# LandCruiser-Controller_1V0.net
KiCad netlist of a schematic drawn in EAGLE
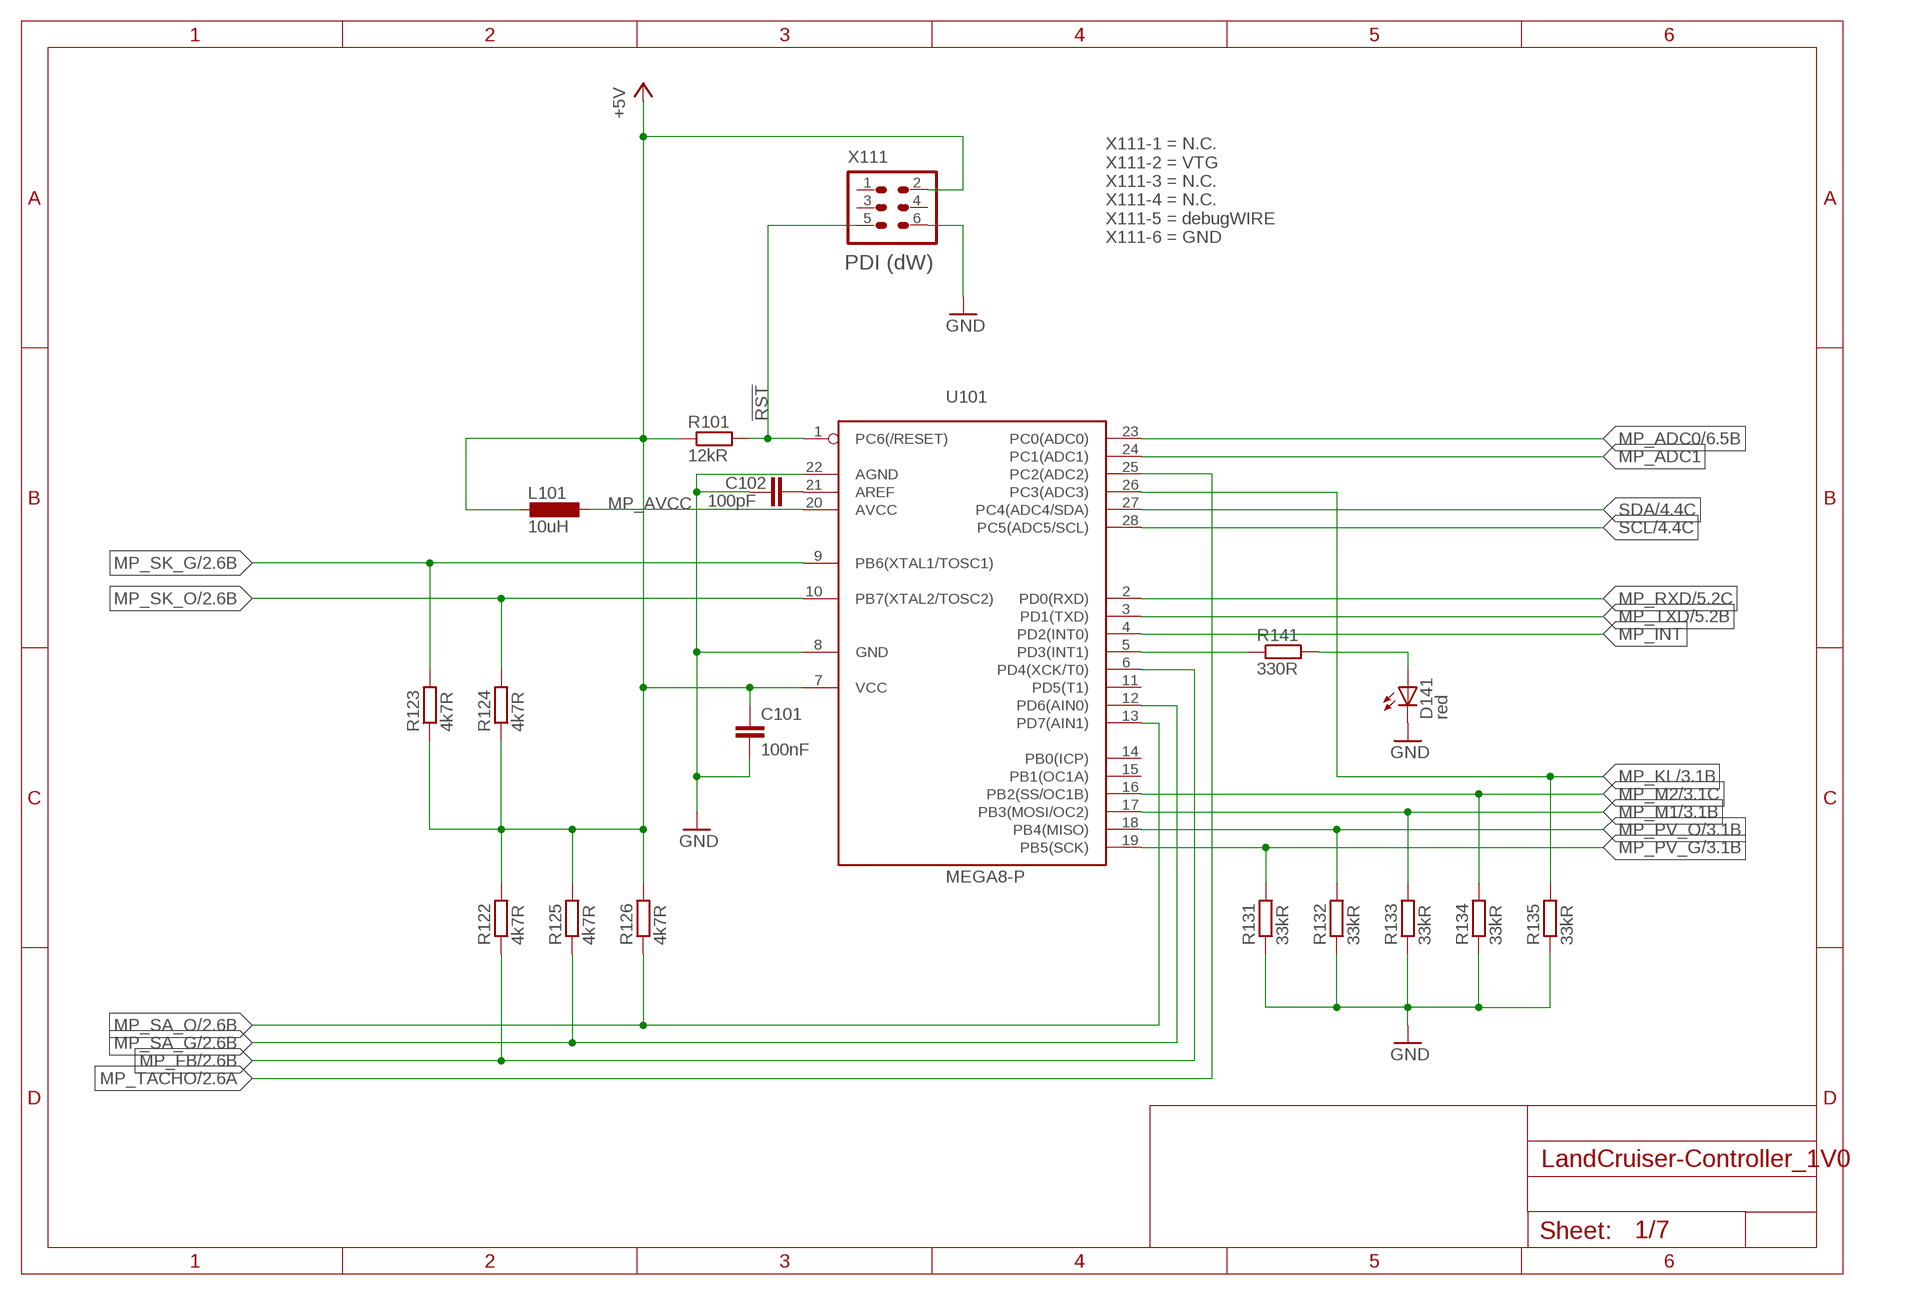
[diagram p0: schematic, sheet 1]
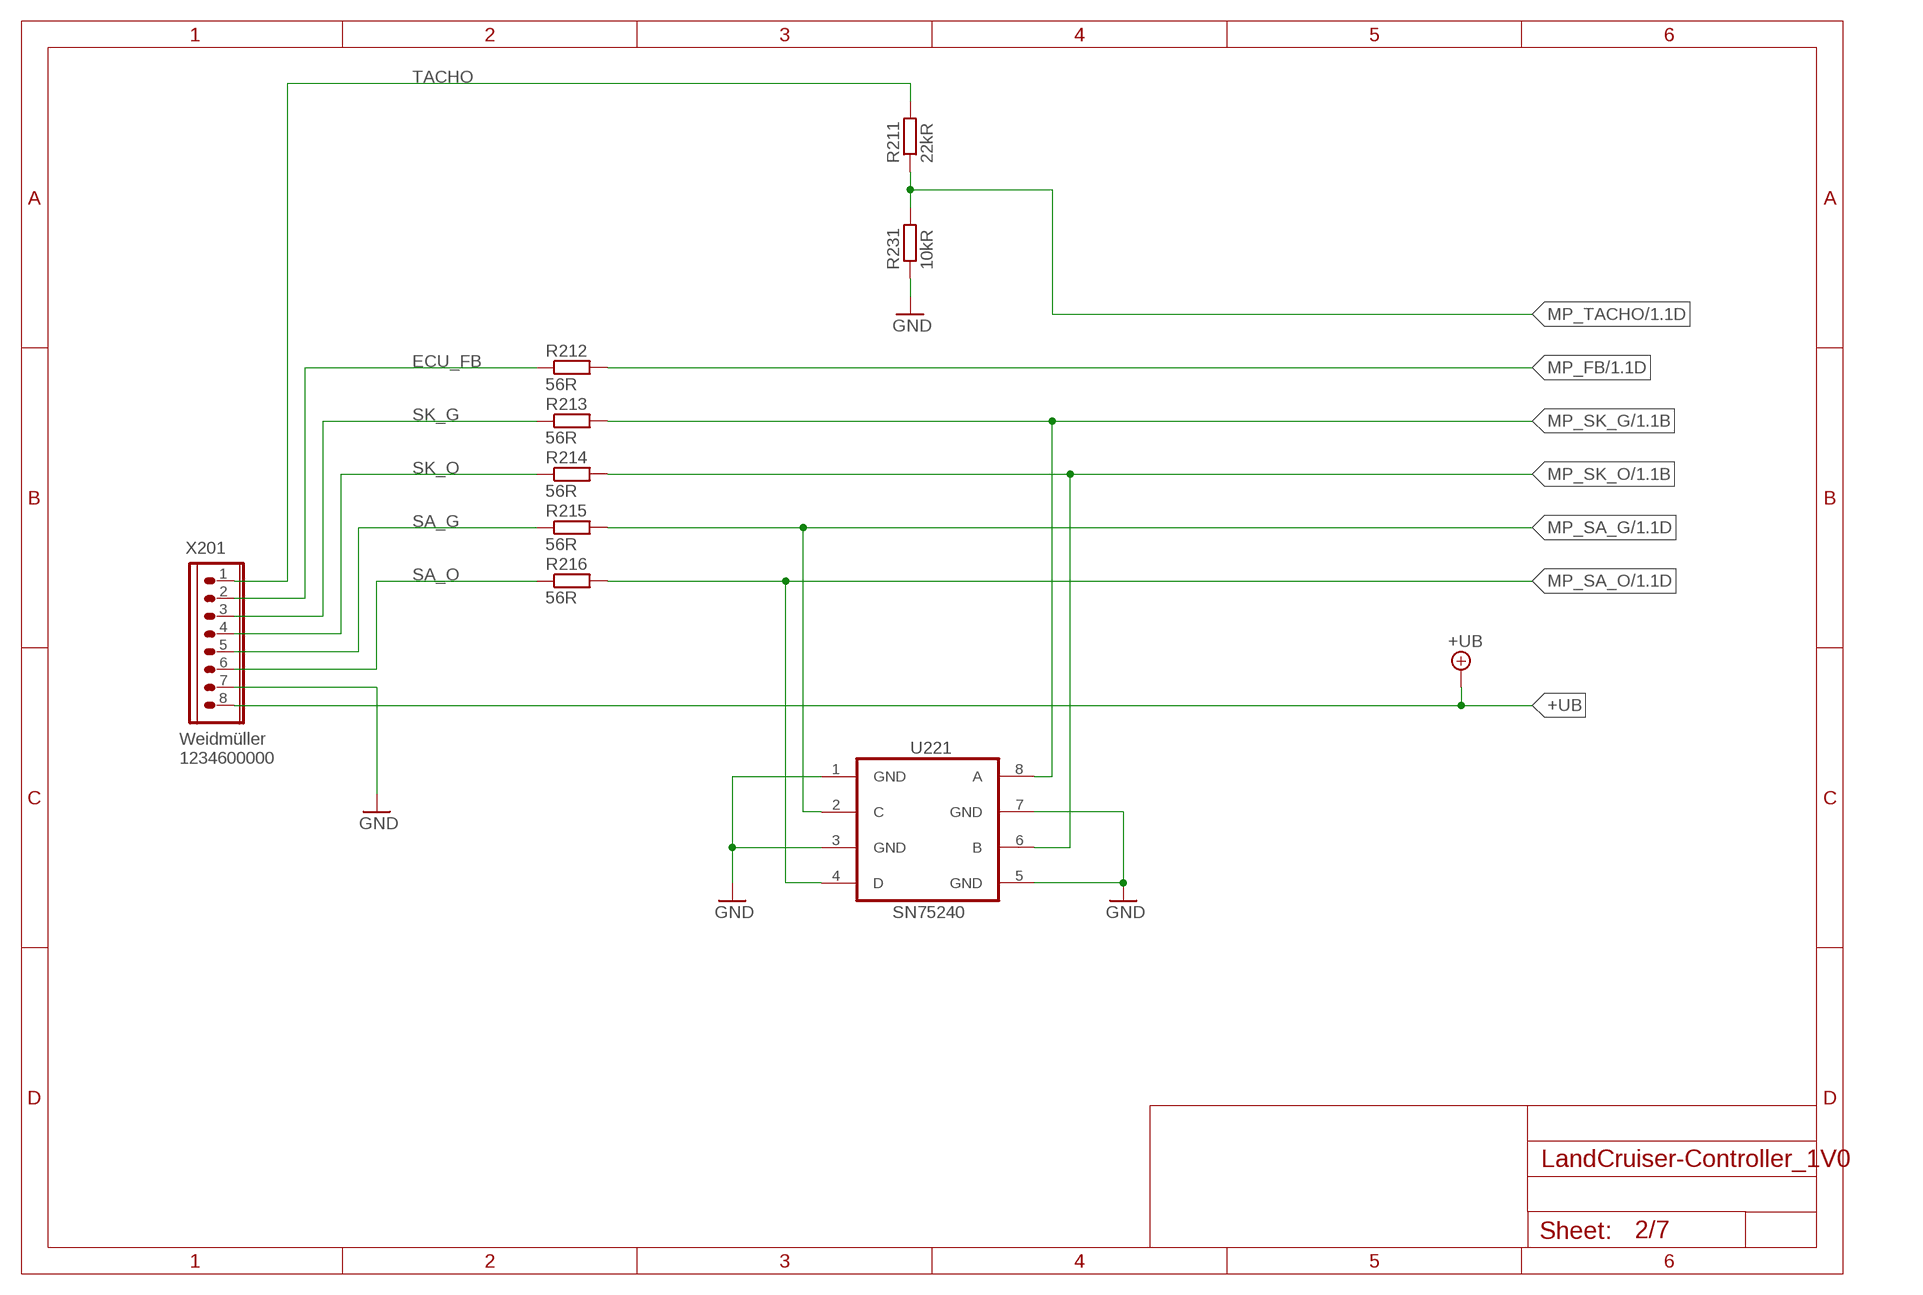
[diagram p1: schematic, sheet 2]
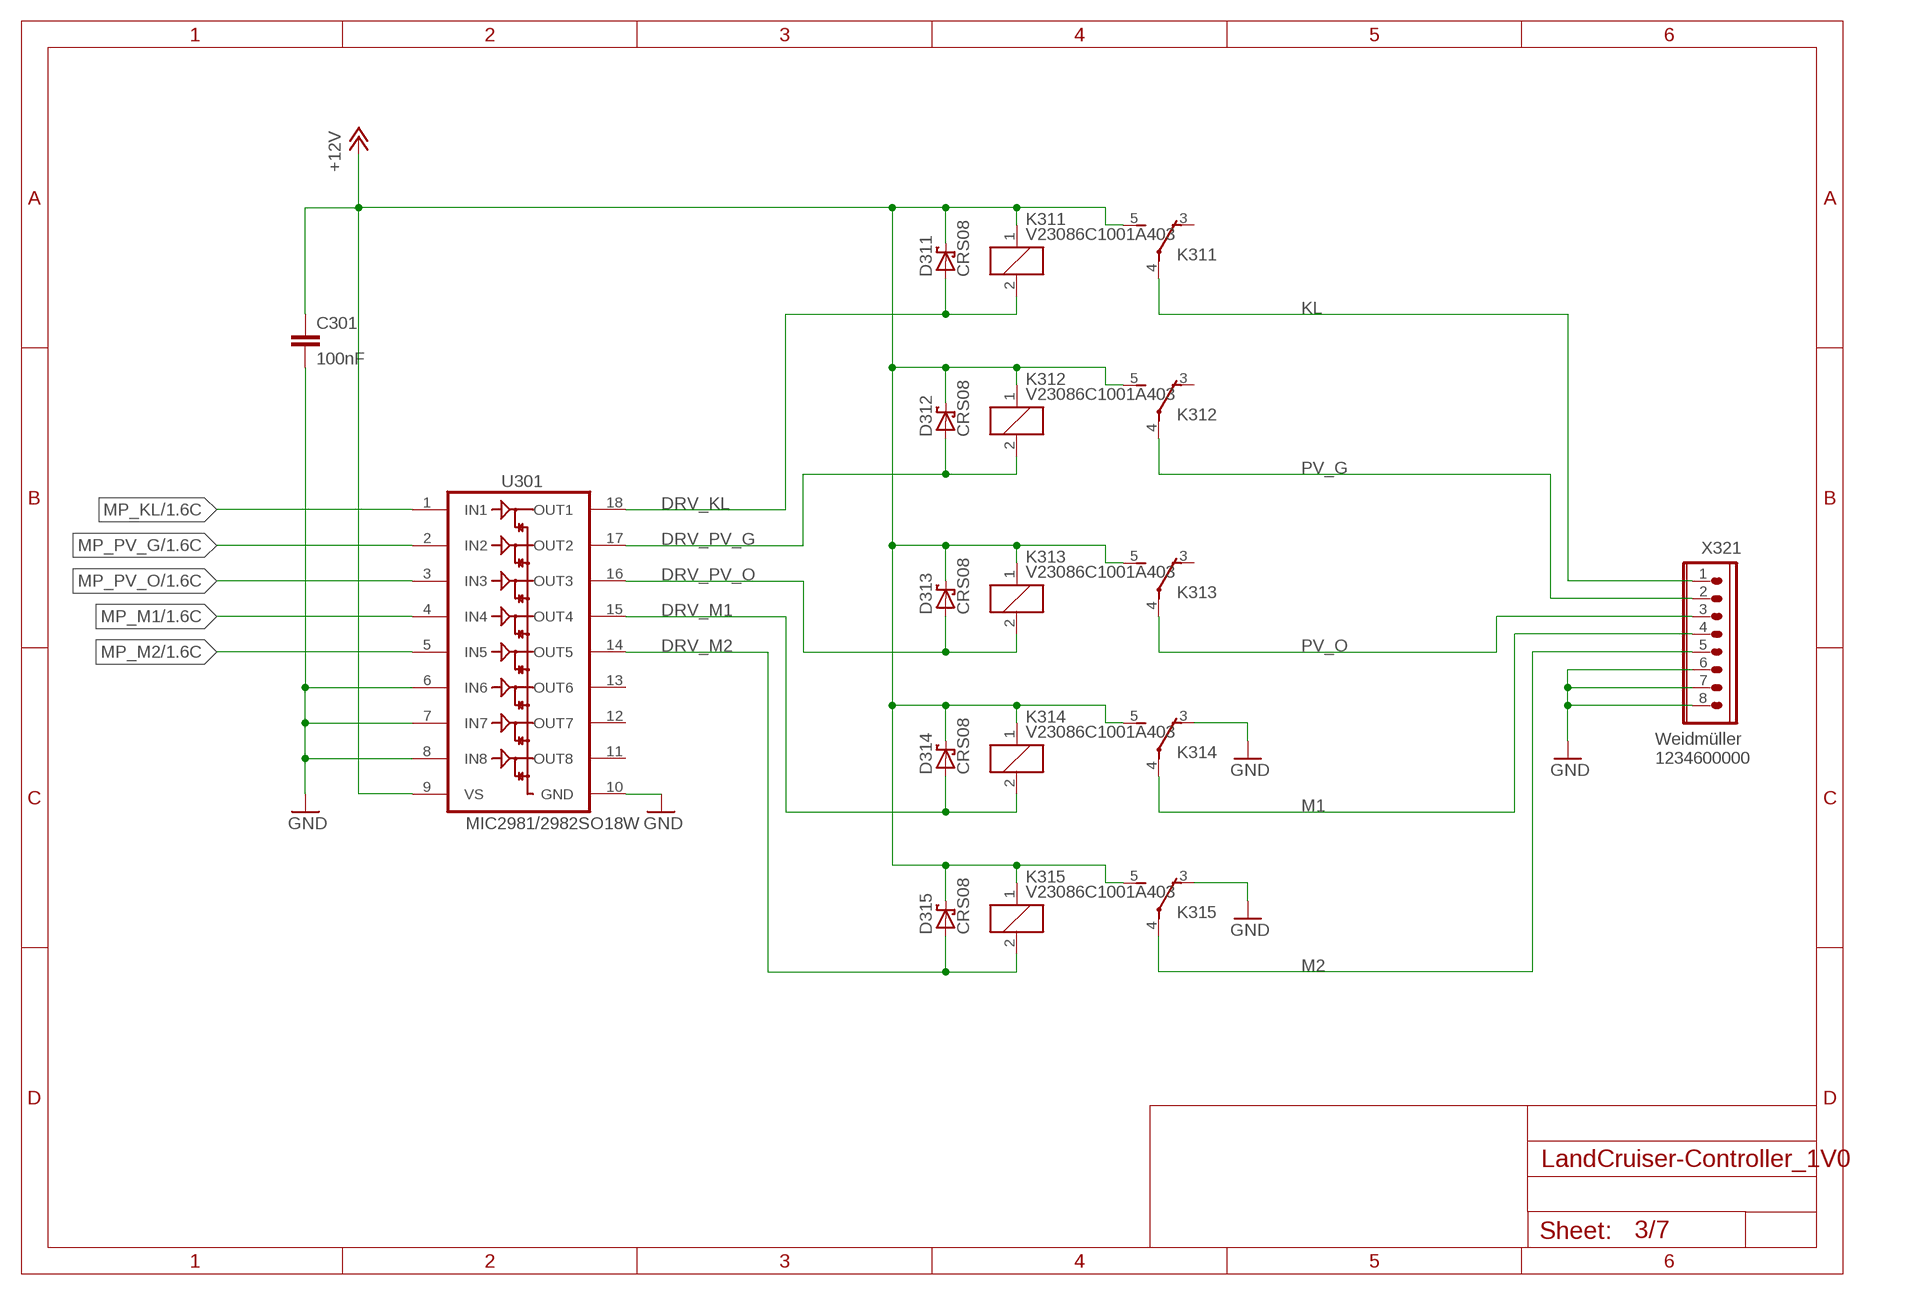
[diagram p2: schematic, sheet 3]
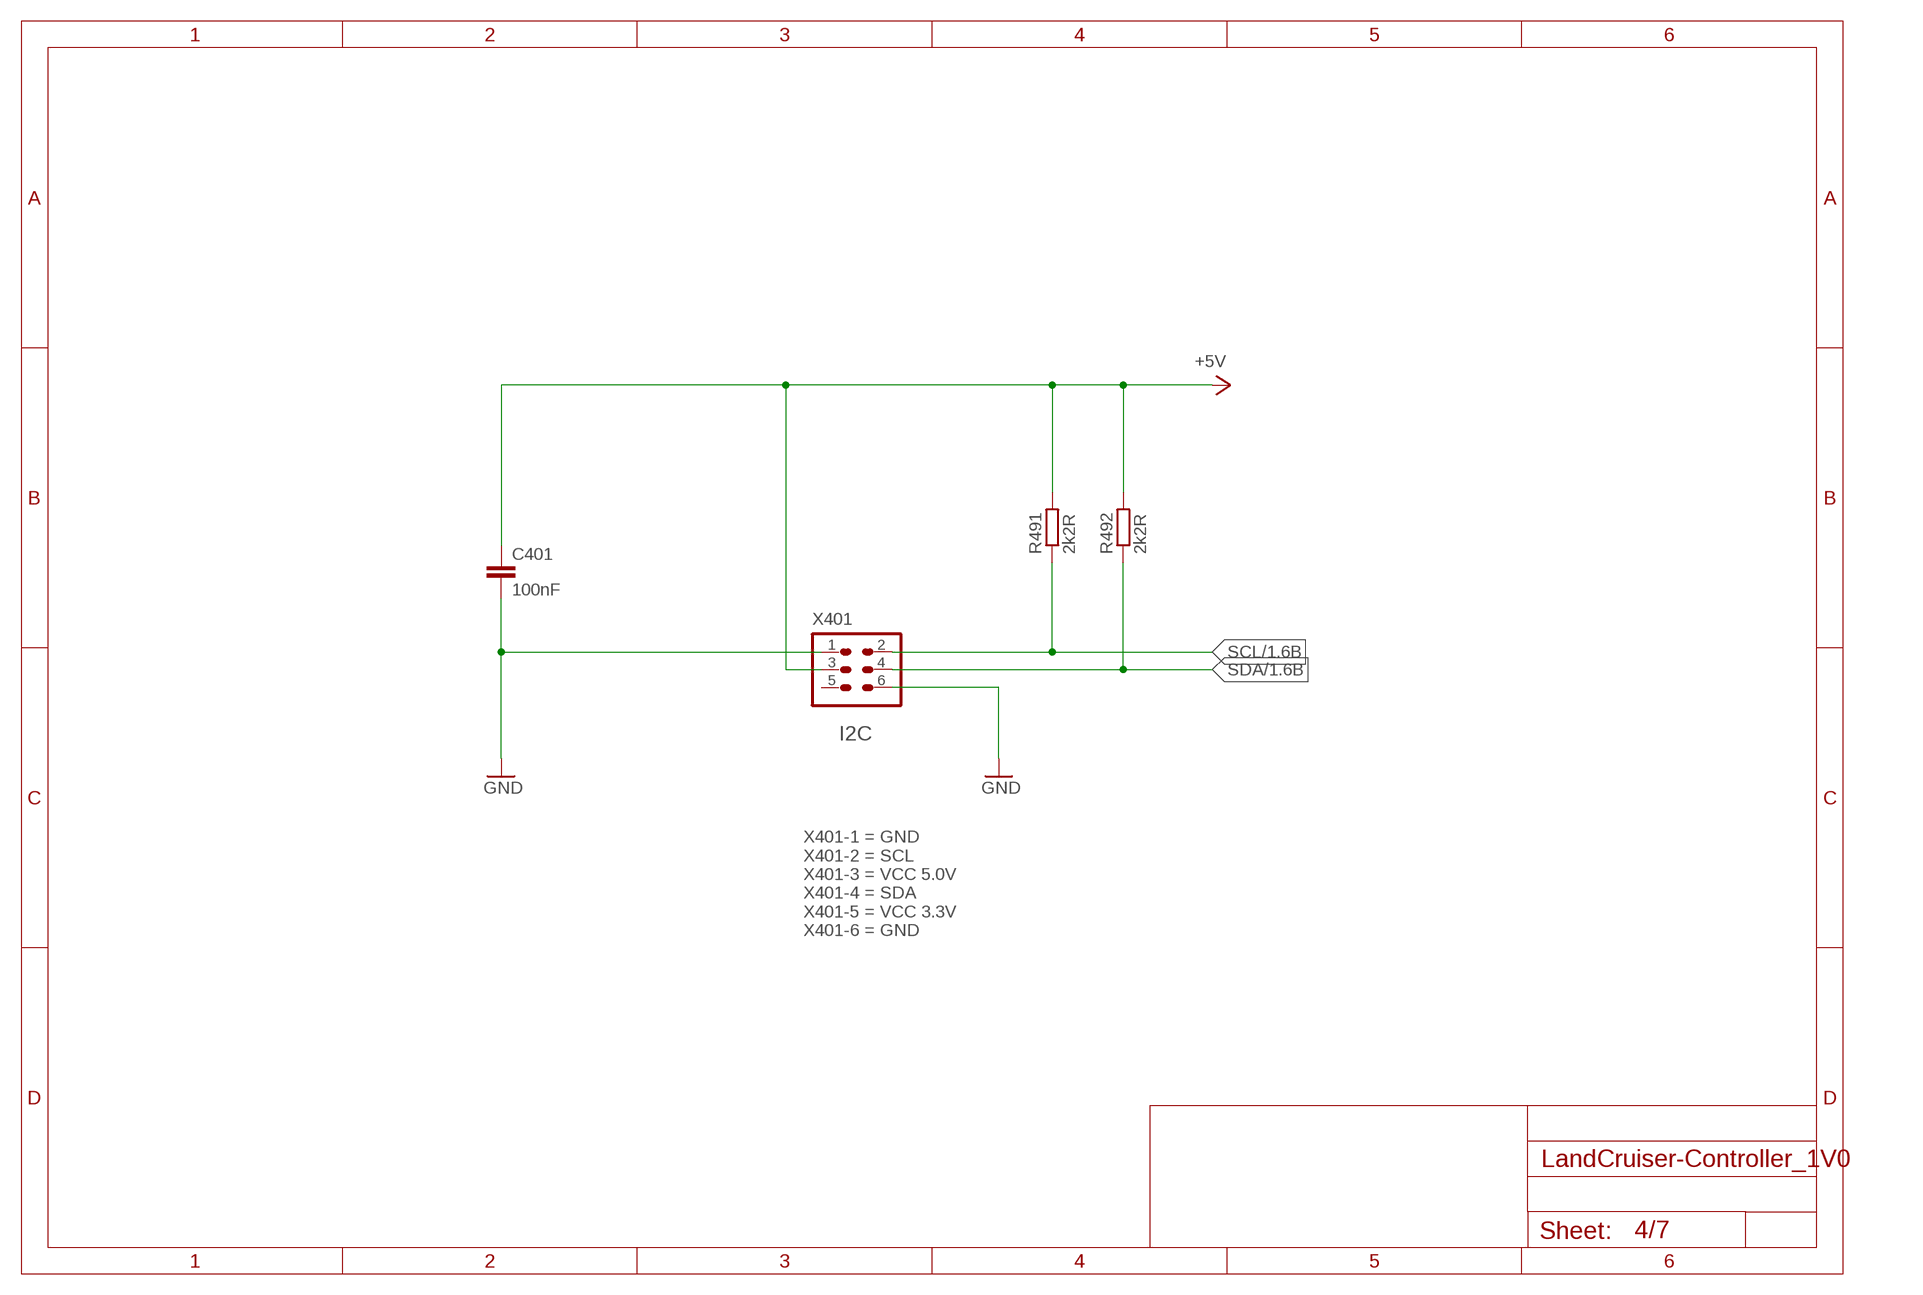
[diagram p3: schematic, sheet 4]
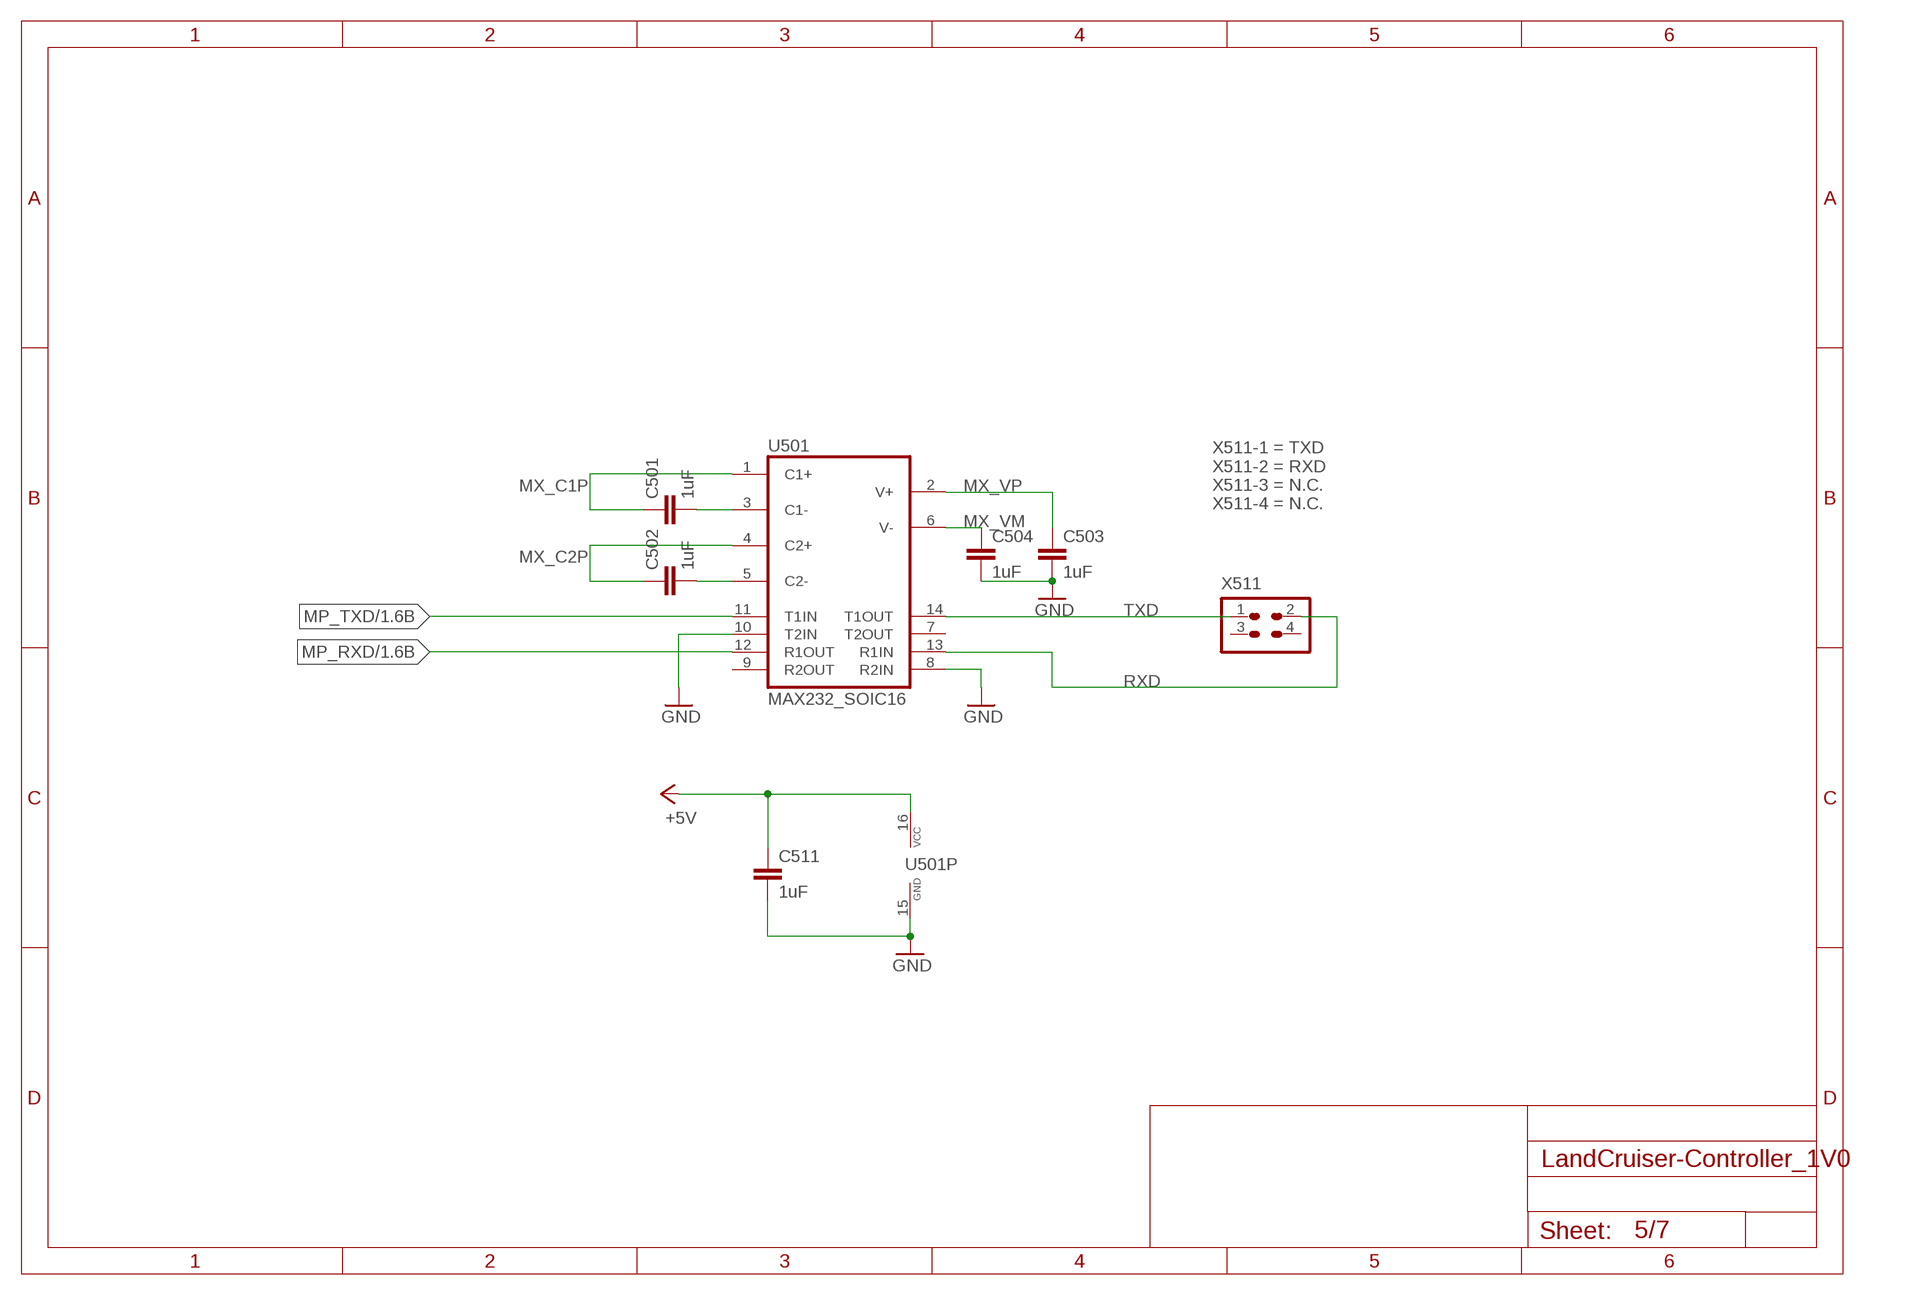
[diagram p4: schematic, sheet 5]
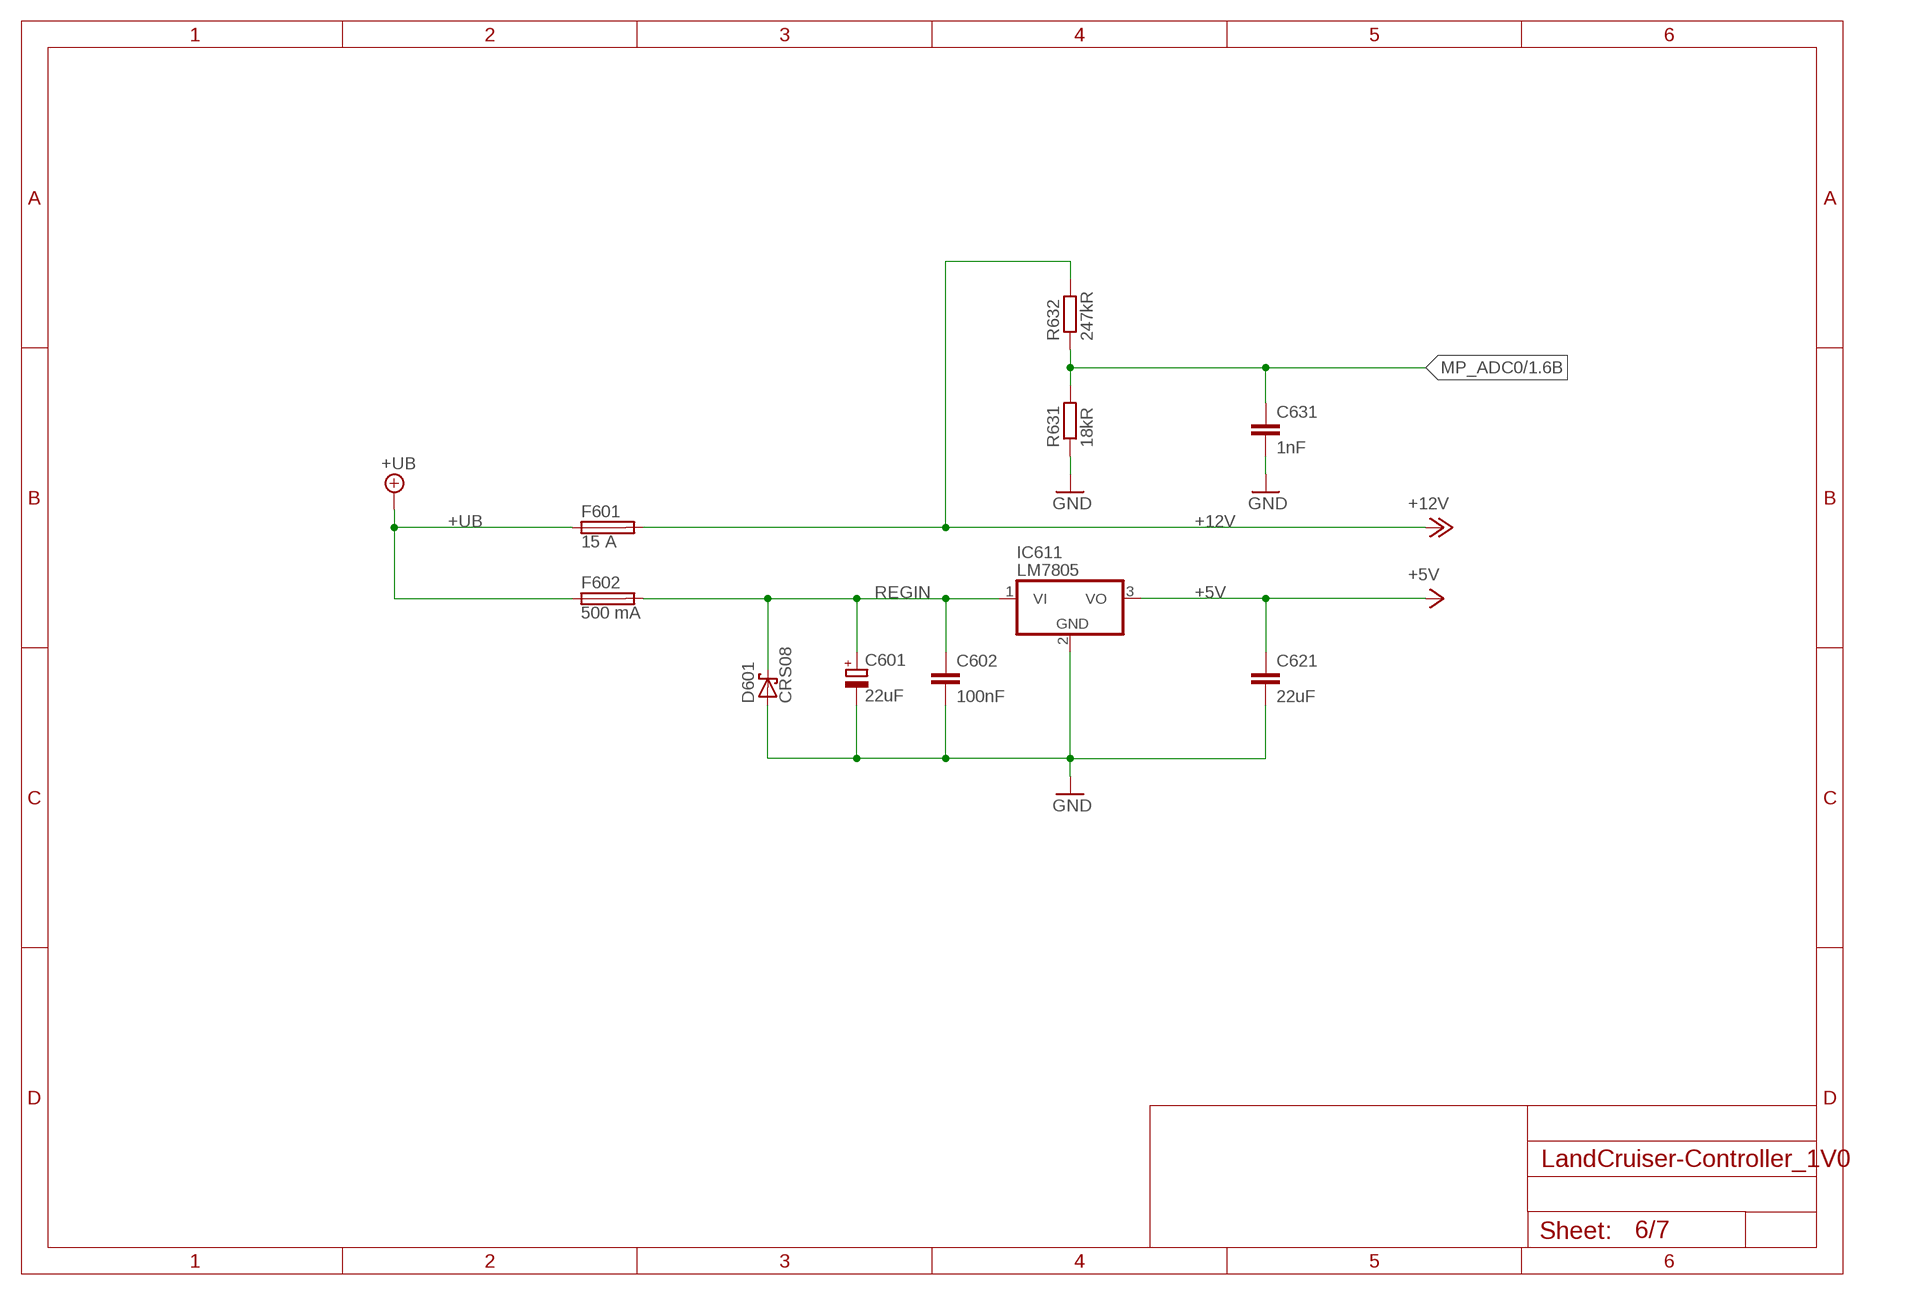
[diagram p5: schematic, sheet 6]
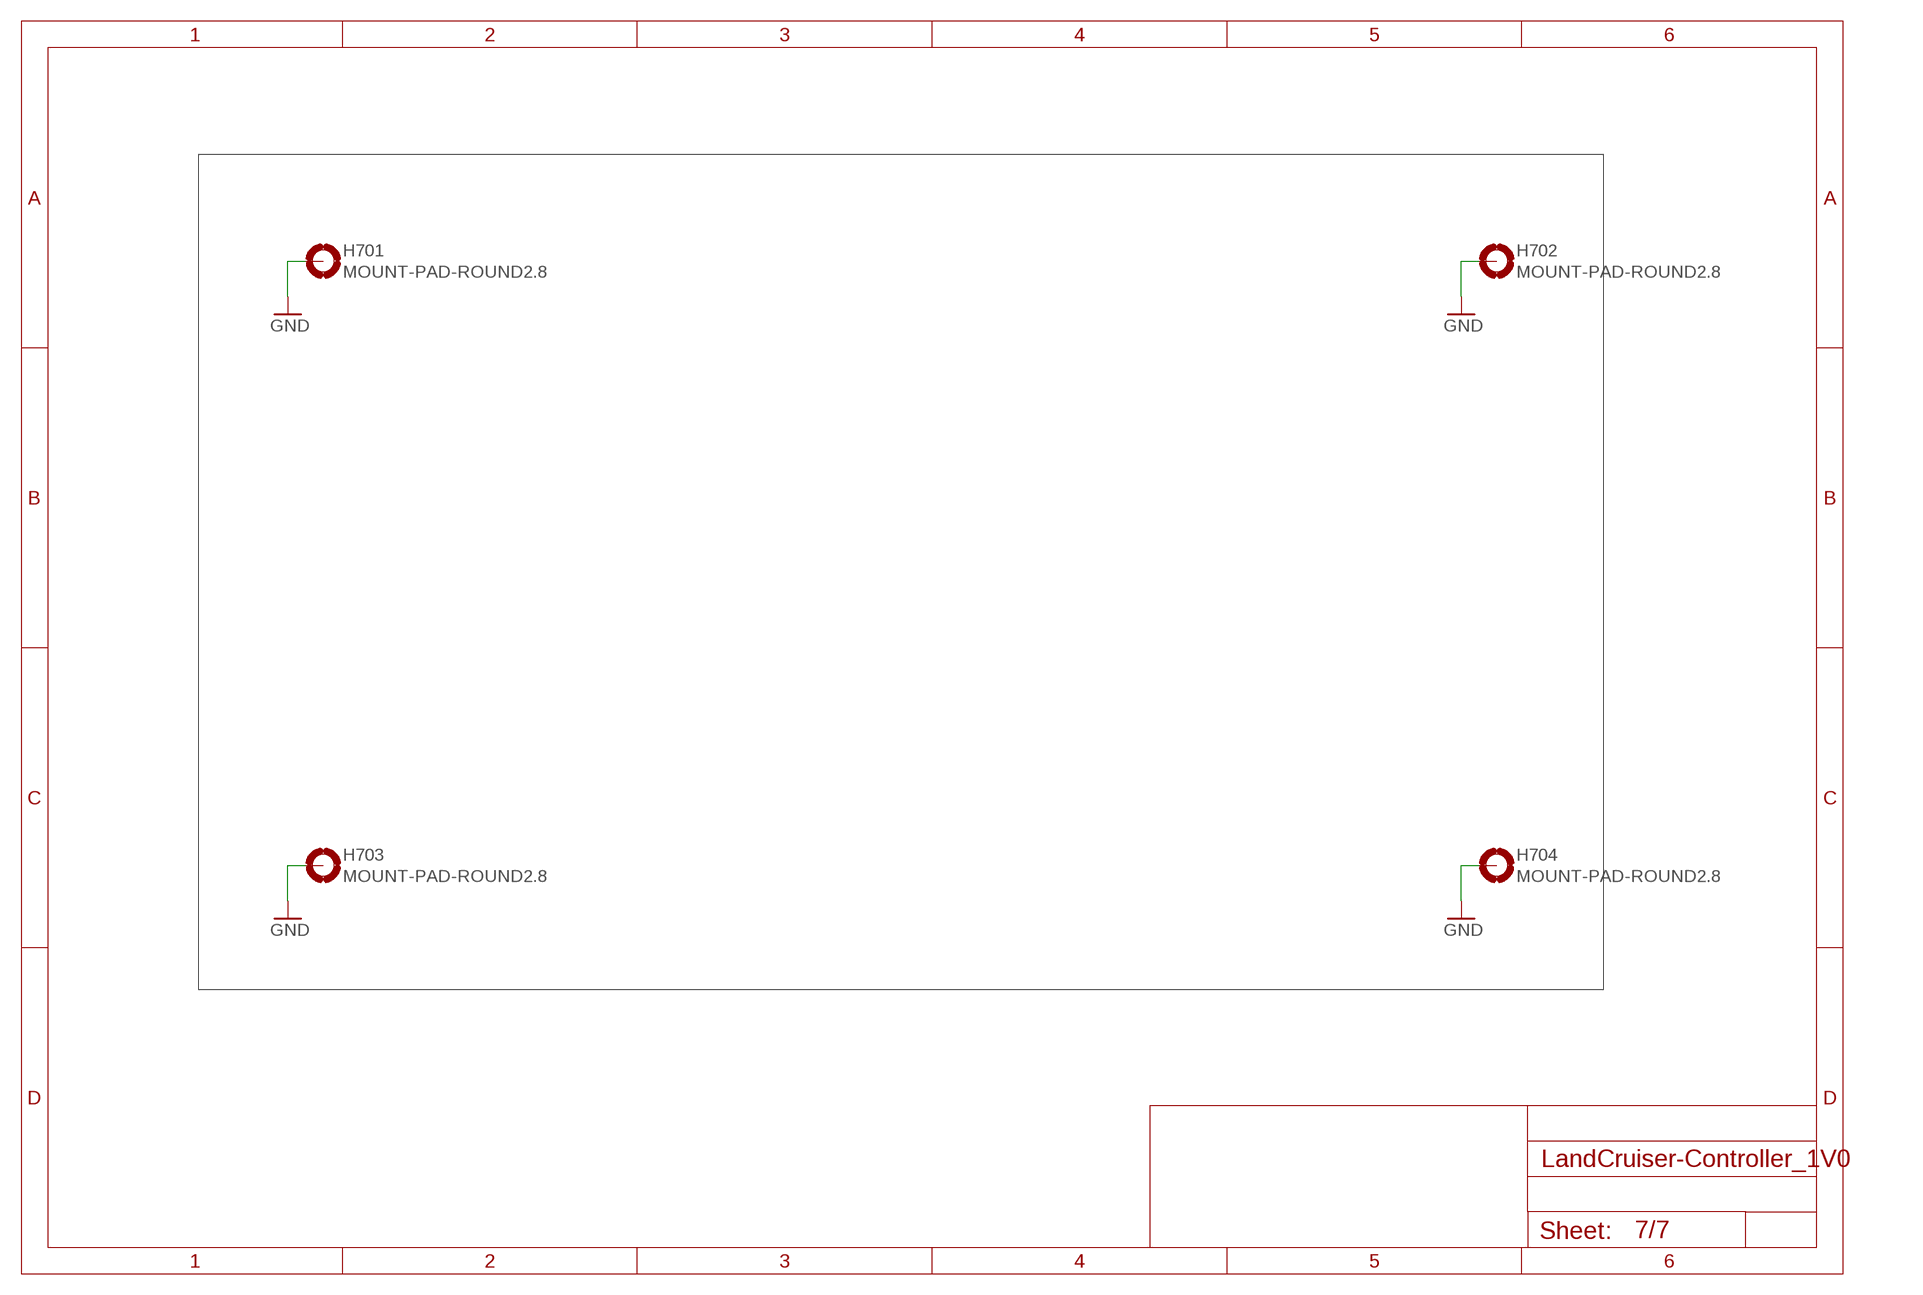
[diagram p6: schematic, sheet 7]

(export (version "E")
  (design (tool "Eeschema 10.0.6"))
  (components
    (comp (ref "C101")
      (value "100nF")
      (footprint "eagle-import:C0805")
      (libsource (lib "eagle-import") (part "C-EUC0805"))
    )
    (comp (ref "C102")
      (value "100pF")
      (footprint "eagle-import:C0805")
      (libsource (lib "eagle-import") (part "C-EUC0805"))
    )
    (comp (ref "D141")
      (value "red")
      (footprint "eagle-import:LED_2PIN-TTH")
      (libsource (lib "eagle-import") (part "LED"))
    )
    (comp (ref "L101")
      (value "10uH")
      (footprint "eagle-import:L1812")
      (libsource (lib "eagle-import") (part "L-EUL1812"))
    )
    (comp (ref "R101")
      (value "12kR")
      (footprint "eagle-import:R0805")
      (libsource (lib "eagle-import") (part "R-EU_R0805"))
    )
    (comp (ref "R122")
      (value "4k7R")
      (footprint "eagle-import:R0805")
      (libsource (lib "eagle-import") (part "R-EU_R0805"))
    )
    (comp (ref "R123")
      (value "4k7R")
      (footprint "eagle-import:R0805")
      (libsource (lib "eagle-import") (part "R-EU_R0805"))
    )
    (comp (ref "R124")
      (value "4k7R")
      (footprint "eagle-import:R0805")
      (libsource (lib "eagle-import") (part "R-EU_R0805"))
    )
    (comp (ref "R125")
      (value "4k7R")
      (footprint "eagle-import:R0805")
      (libsource (lib "eagle-import") (part "R-EU_R0805"))
    )
    (comp (ref "R126")
      (value "4k7R")
      (footprint "eagle-import:R0805")
      (libsource (lib "eagle-import") (part "R-EU_R0805"))
    )
    (comp (ref "R131")
      (value "33kR")
      (footprint "eagle-import:R0805")
      (libsource (lib "eagle-import") (part "R-EU_R0805"))
    )
    (comp (ref "R132")
      (value "33kR")
      (footprint "eagle-import:R0805")
      (libsource (lib "eagle-import") (part "R-EU_R0805"))
    )
    (comp (ref "R133")
      (value "33kR")
      (footprint "eagle-import:R0805")
      (libsource (lib "eagle-import") (part "R-EU_R0805"))
    )
    (comp (ref "R134")
      (value "33kR")
      (footprint "eagle-import:R0805")
      (libsource (lib "eagle-import") (part "R-EU_R0805"))
    )
    (comp (ref "R135")
      (value "33kR")
      (footprint "eagle-import:R0805")
      (libsource (lib "eagle-import") (part "R-EU_R0805"))
    )
    (comp (ref "R141")
      (value "330R")
      (footprint "eagle-import:R0805")
      (libsource (lib "eagle-import") (part "R-EU_R0805"))
    )
    (comp (ref "U101")
      (value "MEGA8-P")
      (footprint "eagle-import:DIL28-3")
      (libsource (lib "eagle-import") (part "MEGA8-P"))
    )
    (comp (ref "X111")
      (value "HEADER-2X3")
      (footprint "eagle-import:2X03")
      (libsource (lib "eagle-import") (part "HEADER-2X3"))
    )
    (comp (ref "C301")
      (value "100nF")
      (footprint "eagle-import:C0805")
      (libsource (lib "eagle-import") (part "C-EUC0805"))
    )
    (comp (ref "D311")
      (value "CRS08")
      (footprint "eagle-import:SOD80C")
      (libsource (lib "eagle-import") (part "CRS08"))
    )
    (comp (ref "D312")
      (value "CRS08")
      (footprint "eagle-import:SOD80C")
      (libsource (lib "eagle-import") (part "CRS08"))
    )
    (comp (ref "D313")
      (value "CRS08")
      (footprint "eagle-import:SOD80C")
      (libsource (lib "eagle-import") (part "CRS08"))
    )
    (comp (ref "D314")
      (value "CRS08")
      (footprint "eagle-import:SOD80C")
      (libsource (lib "eagle-import") (part "CRS08"))
    )
    (comp (ref "D315")
      (value "CRS08")
      (footprint "eagle-import:SOD80C")
      (libsource (lib "eagle-import") (part "CRS08"))
    )
    (comp (ref "K311")
      (value "V23086C1001A403")
      (footprint "eagle-import:V23086-CO")
      (libsource (lib "eagle-import") (part "V23086C1001A403"))
    )
    (comp (ref "K312")
      (value "V23086C1001A403")
      (footprint "eagle-import:V23086-CO")
      (libsource (lib "eagle-import") (part "V23086C1001A403"))
    )
    (comp (ref "K313")
      (value "V23086C1001A403")
      (footprint "eagle-import:V23086-CO")
      (libsource (lib "eagle-import") (part "V23086C1001A403"))
    )
    (comp (ref "K314")
      (value "V23086C1001A403")
      (footprint "eagle-import:V23086-CO")
      (libsource (lib "eagle-import") (part "V23086C1001A403"))
    )
    (comp (ref "K315")
      (value "V23086C1001A403")
      (footprint "eagle-import:V23086-CO")
      (libsource (lib "eagle-import") (part "V23086C1001A403"))
    )
    (comp (ref "U301")
      (value "MIC2981/2982SO18W")
      (footprint "eagle-import:SO-18W")
      (fields (field (name "MF") "MICROCHIP") (field (name "MP") "MIC2981/82YWM-TR"))
      (libsource (lib "eagle-import") (part "MIC2981/2982SO18W"))
    )
    (comp (ref "X321")
      (value "WEIDMUELLER 1234600000")
      (footprint "eagle-import:WIRE-TO-BOARD_5MM08_1X08")
      (libsource (lib "eagle-import") (part "WIRE-TO-BOARD_5MM08_1X08"))
    )
    (comp (ref "C401")
      (value "100nF")
      (footprint "eagle-import:C0805")
      (libsource (lib "eagle-import") (part "C-EUC0805"))
    )
    (comp (ref "R491")
      (value "2k2R")
      (footprint "eagle-import:R0805")
      (libsource (lib "eagle-import") (part "R-EU_R0805"))
    )
    (comp (ref "R492")
      (value "2k2R")
      (footprint "eagle-import:R0805")
      (libsource (lib "eagle-import") (part "R-EU_R0805"))
    )
    (comp (ref "X401")
      (value "I2C")
      (footprint "eagle-import:2X03")
      (libsource (lib "eagle-import") (part "HEADER-2X3"))
    )
    (comp (ref "R211")
      (value "22kR")
      (footprint "eagle-import:R0805")
      (libsource (lib "eagle-import") (part "R-EU_R0805"))
    )
    (comp (ref "R212")
      (value "56R")
      (footprint "eagle-import:R0805")
      (libsource (lib "eagle-import") (part "R-EU_R0805"))
    )
    (comp (ref "R213")
      (value "56R")
      (footprint "eagle-import:R0805")
      (libsource (lib "eagle-import") (part "R-EU_R0805"))
    )
    (comp (ref "R214")
      (value "56R")
      (footprint "eagle-import:R0805")
      (libsource (lib "eagle-import") (part "R-EU_R0805"))
    )
    (comp (ref "R215")
      (value "56R")
      (footprint "eagle-import:R0805")
      (libsource (lib "eagle-import") (part "R-EU_R0805"))
    )
    (comp (ref "R216")
      (value "56R")
      (footprint "eagle-import:R0805")
      (libsource (lib "eagle-import") (part "R-EU_R0805"))
    )
    (comp (ref "R231")
      (value "10kR")
      (footprint "eagle-import:R0805")
      (libsource (lib "eagle-import") (part "R-EU_R0805"))
    )
    (comp (ref "U221")
      (value "SN75240")
      (footprint "eagle-import:TSSOP-8")
      (libsource (lib "eagle-import") (part "SN75240"))
    )
    (comp (ref "X201")
      (value "WEIDMUELLER 1234600000")
      (footprint "eagle-import:WIRE-TO-BOARD_5MM08_1X08")
      (libsource (lib "eagle-import") (part "WIRE-TO-BOARD_5MM08_1X08"))
    )
    (comp (ref "C601")
      (value "22uF")
      (footprint "eagle-import:E2,5-7")
      (libsource (lib "eagle-import") (part "CPOL-EUE2.5-7"))
    )
    (comp (ref "C602")
      (value "100nF")
      (footprint "eagle-import:C0805")
      (libsource (lib "eagle-import") (part "C-EUC0805"))
    )
    (comp (ref "C621")
      (value "22uF")
      (footprint "eagle-import:C0805")
      (libsource (lib "eagle-import") (part "C-EUC0805"))
    )
    (comp (ref "C631")
      (value "1nF")
      (footprint "eagle-import:C0805")
      (libsource (lib "eagle-import") (part "C-EUC0805"))
    )
    (comp (ref "D601")
      (value "CRS08")
      (footprint "eagle-import:SOD80C")
      (libsource (lib "eagle-import") (part "CRS08"))
    )
    (comp (ref "F601")
      (value "15 A")
      (footprint "eagle-import:MCCQ-121")
      (fields (field (name "MF") "MINICOMP") (field (name "MPN") "MCCQ-121"))
      (libsource (lib "eagle-import") (part "MCCQ-121"))
    )
    (comp (ref "F602")
      (value "500 mA")
      (footprint "eagle-import:MCCQ-121")
      (fields (field (name "MF") "MINICOMP") (field (name "MPN") "MCCQ-121"))
      (libsource (lib "eagle-import") (part "MCCQ-121"))
    )
    (comp (ref "IC611")
      (value "LM7805")
      (footprint "eagle-import:TO220H")
      (libsource (lib "eagle-import") (part "78T05"))
    )
    (comp (ref "R631")
      (value "18kR")
      (footprint "eagle-import:R0805")
      (libsource (lib "eagle-import") (part "R-EU_R0805"))
    )
    (comp (ref "R632")
      (value "247kR")
      (footprint "eagle-import:R0805")
      (libsource (lib "eagle-import") (part "R-EU_R0805"))
    )
    (comp (ref "C501")
      (value "1uF")
      (footprint "eagle-import:C0805")
      (libsource (lib "eagle-import") (part "C-EUC0805"))
    )
    (comp (ref "C502")
      (value "1uF")
      (footprint "eagle-import:C0805")
      (libsource (lib "eagle-import") (part "C-EUC0805"))
    )
    (comp (ref "C503")
      (value "1uF")
      (footprint "eagle-import:C0805")
      (libsource (lib "eagle-import") (part "C-EUC0805"))
    )
    (comp (ref "C504")
      (value "1uF")
      (footprint "eagle-import:C0805")
      (libsource (lib "eagle-import") (part "C-EUC0805"))
    )
    (comp (ref "C511")
      (value "1uF")
      (footprint "eagle-import:C0805")
      (libsource (lib "eagle-import") (part "C-EUC0805"))
    )
    (comp (ref "U501")
      (value "MAX232_SOIC16")
      (footprint "eagle-import:SOIC16N")
      (fields (field (name "MF") "MAXIM") (field (name "MPN") "MAX232ECDR"))
      (libsource (lib "eagle-import") (part "MAX232_SOIC16"))
    )
    (comp (ref "X511")
      (value "HEADER-2X2")
      (footprint "eagle-import:2X02")
      (libsource (lib "eagle-import") (part "HEADER-2X2"))
    )
    (comp (ref "H701")
      (value "MOUNT-PAD-ROUND2.8")
      (footprint "eagle-import:2,8-PAD")
      (libsource (lib "eagle-import") (part "MOUNT-PAD-ROUND2.8"))
    )
    (comp (ref "H702")
      (value "MOUNT-PAD-ROUND2.8")
      (footprint "eagle-import:2,8-PAD")
      (libsource (lib "eagle-import") (part "MOUNT-PAD-ROUND2.8"))
    )
    (comp (ref "H703")
      (value "MOUNT-PAD-ROUND2.8")
      (footprint "eagle-import:2,8-PAD")
      (libsource (lib "eagle-import") (part "MOUNT-PAD-ROUND2.8"))
    )
    (comp (ref "H704")
      (value "MOUNT-PAD-ROUND2.8")
      (footprint "eagle-import:2,8-PAD")
      (libsource (lib "eagle-import") (part "MOUNT-PAD-ROUND2.8"))
    )
  )
  (nets
    (net (code "1") (name "+5V") (class "Default")
      (node (ref "C101") (pin "1") (pinfunction "1_1") (pintype "passive"))
      (node (ref "C401") (pin "1") (pinfunction "1_1") (pintype "passive"))
      (node (ref "C511") (pin "1") (pinfunction "1_1") (pintype "passive"))
      (node (ref "C621") (pin "1") (pinfunction "1_1") (pintype "passive"))
      (node (ref "IC611") (pin "3") (pinfunction "VO_3") (pintype "passive"))
      (node (ref "L101") (pin "2") (pinfunction "2_2") (pintype "passive"))
      (node (ref "R101") (pin "1") (pinfunction "1_1") (pintype "passive"))
      (node (ref "R122") (pin "2") (pinfunction "2_2") (pintype "passive"))
      (node (ref "R123") (pin "1") (pinfunction "1_1") (pintype "passive"))
      (node (ref "R124") (pin "1") (pinfunction "1_1") (pintype "passive"))
      (node (ref "R125") (pin "2") (pinfunction "2_2") (pintype "passive"))
      (node (ref "R126") (pin "2") (pinfunction "2_2") (pintype "passive"))
      (node (ref "R491") (pin "2") (pinfunction "2_2") (pintype "passive"))
      (node (ref "R492") (pin "2") (pinfunction "2_2") (pintype "passive"))
      (node (ref "U101") (pin "7") (pinfunction "VCC_7") (pintype "bidirectional"))
      (node (ref "U501") (pin "16") (pinfunction "VCC_16") (pintype "power_in"))
      (node (ref "X111") (pin "2") (pinfunction "2_2") (pintype "passive"))
      (node (ref "X401") (pin "3") (pinfunction "3_3") (pintype "passive"))
    )
    (net (code "2") (name "+12V") (class "Default")
      (node (ref "C301") (pin "1") (pinfunction "1_1") (pintype "passive"))
      (node (ref "D311") (pin "C") (pinfunction "C_C") (pintype "passive"))
      (node (ref "D312") (pin "C") (pinfunction "C_C") (pintype "passive"))
      (node (ref "D313") (pin "C") (pinfunction "C_C") (pintype "passive"))
      (node (ref "D314") (pin "C") (pinfunction "C_C") (pintype "passive"))
      (node (ref "D315") (pin "C") (pinfunction "C_C") (pintype "passive"))
      (node (ref "F601") (pin "3") (pinfunction "2_3") (pintype "passive"))
      (node (ref "F601") (pin "4") (pinfunction "2_4") (pintype "passive"))
      (node (ref "K311") (pin "1") (pinfunction "1_1") (pintype "passive"))
      (node (ref "K311") (pin "5") (pinfunction "S_5") (pintype "passive"))
      (node (ref "K312") (pin "1") (pinfunction "1_1") (pintype "passive"))
      (node (ref "K312") (pin "5") (pinfunction "S_5") (pintype "passive"))
      (node (ref "K313") (pin "1") (pinfunction "1_1") (pintype "passive"))
      (node (ref "K313") (pin "5") (pinfunction "S_5") (pintype "passive"))
      (node (ref "K314") (pin "1") (pinfunction "1_1") (pintype "passive"))
      (node (ref "K314") (pin "5") (pinfunction "S_5") (pintype "passive"))
      (node (ref "K315") (pin "1") (pinfunction "1_1") (pintype "passive"))
      (node (ref "K315") (pin "5") (pinfunction "S_5") (pintype "passive"))
      (node (ref "R632") (pin "2") (pinfunction "2_2") (pintype "passive"))
      (node (ref "U301") (pin "9") (pinfunction "VS_9") (pintype "power_in"))
    )
    (net (code "3") (name "+UB") (class "Default")
      (node (ref "F601") (pin "1") (pinfunction "1_1") (pintype "passive"))
      (node (ref "F601") (pin "2") (pinfunction "1_2") (pintype "passive"))
      (node (ref "F602") (pin "1") (pinfunction "1_1") (pintype "passive"))
      (node (ref "F602") (pin "2") (pinfunction "1_2") (pintype "passive"))
      (node (ref "X201") (pin "8") (pinfunction "8_8") (pintype "passive"))
    )
    (net (code "4") (name "DRV_KL") (class "Default")
      (node (ref "D311") (pin "A") (pinfunction "A_A") (pintype "passive"))
      (node (ref "K311") (pin "2") (pinfunction "2_2") (pintype "passive"))
      (node (ref "U301") (pin "18") (pinfunction "OUT1_18") (pintype "open_collector"))
    )
    (net (code "5") (name "DRV_M1") (class "Default")
      (node (ref "D314") (pin "A") (pinfunction "A_A") (pintype "passive"))
      (node (ref "K314") (pin "2") (pinfunction "2_2") (pintype "passive"))
      (node (ref "U301") (pin "15") (pinfunction "OUT4_15") (pintype "open_collector"))
    )
    (net (code "6") (name "DRV_M2") (class "Default")
      (node (ref "D315") (pin "A") (pinfunction "A_A") (pintype "passive"))
      (node (ref "K315") (pin "2") (pinfunction "2_2") (pintype "passive"))
      (node (ref "U301") (pin "14") (pinfunction "OUT5_14") (pintype "open_collector"))
    )
    (net (code "7") (name "DRV_PV_G") (class "Default")
      (node (ref "D312") (pin "A") (pinfunction "A_A") (pintype "passive"))
      (node (ref "K312") (pin "2") (pinfunction "2_2") (pintype "passive"))
      (node (ref "U301") (pin "17") (pinfunction "OUT2_17") (pintype "open_collector"))
    )
    (net (code "8") (name "DRV_PV_O") (class "Default")
      (node (ref "D313") (pin "A") (pinfunction "A_A") (pintype "passive"))
      (node (ref "K313") (pin "2") (pinfunction "2_2") (pintype "passive"))
      (node (ref "U301") (pin "16") (pinfunction "OUT3_16") (pintype "open_collector"))
    )
    (net (code "9") (name "ECU_FB") (class "Default")
      (node (ref "R212") (pin "1") (pinfunction "1_1") (pintype "passive"))
      (node (ref "X201") (pin "2") (pinfunction "2_2") (pintype "passive"))
    )
    (net (code "10") (name "GND") (class "Default")
      (node (ref "C101") (pin "2") (pinfunction "2_2") (pintype "passive"))
      (node (ref "C102") (pin "1") (pinfunction "1_1") (pintype "passive"))
      (node (ref "C301") (pin "2") (pinfunction "2_2") (pintype "passive"))
      (node (ref "C401") (pin "2") (pinfunction "2_2") (pintype "passive"))
      (node (ref "C503") (pin "2") (pinfunction "2_2") (pintype "passive"))
      (node (ref "C504") (pin "2") (pinfunction "2_2") (pintype "passive"))
      (node (ref "C511") (pin "2") (pinfunction "2_2") (pintype "passive"))
      (node (ref "C601") (pin "-") (pinfunction "-_-") (pintype "passive"))
      (node (ref "C602") (pin "2") (pinfunction "2_2") (pintype "passive"))
      (node (ref "C621") (pin "2") (pinfunction "2_2") (pintype "passive"))
      (node (ref "C631") (pin "2") (pinfunction "2_2") (pintype "passive"))
      (node (ref "D141") (pin "C") (pinfunction "C_C") (pintype "passive"))
      (node (ref "D601") (pin "A") (pinfunction "A_A") (pintype "passive"))
      (node (ref "H701") (pin "B2,8") (pinfunction "MOUNT_B2,8") (pintype "passive"))
      (node (ref "H702") (pin "B2,8") (pinfunction "MOUNT_B2,8") (pintype "passive"))
      (node (ref "H703") (pin "B2,8") (pinfunction "MOUNT_B2,8") (pintype "passive"))
      (node (ref "H704") (pin "B2,8") (pinfunction "MOUNT_B2,8") (pintype "passive"))
      (node (ref "IC611") (pin "2") (pinfunction "GND_2") (pintype "passive"))
      (node (ref "K314") (pin "3") (pinfunction "O_3") (pintype "passive"))
      (node (ref "K315") (pin "3") (pinfunction "O_3") (pintype "passive"))
      (node (ref "R131") (pin "1") (pinfunction "1_1") (pintype "passive"))
      (node (ref "R132") (pin "1") (pinfunction "1_1") (pintype "passive"))
      (node (ref "R133") (pin "1") (pinfunction "1_1") (pintype "passive"))
      (node (ref "R134") (pin "1") (pinfunction "1_1") (pintype "passive"))
      (node (ref "R135") (pin "1") (pinfunction "1_1") (pintype "passive"))
      (node (ref "R231") (pin "1") (pinfunction "1_1") (pintype "passive"))
      (node (ref "R631") (pin "1") (pinfunction "1_1") (pintype "passive"))
      (node (ref "U101") (pin "22") (pinfunction "AGND_22") (pintype "bidirectional"))
      (node (ref "U101") (pin "8") (pinfunction "GND_8") (pintype "bidirectional"))
      (node (ref "U221") (pin "1") (pinfunction "GND_1") (pintype "power_in"))
      (node (ref "U221") (pin "3") (pinfunction "GND_3") (pintype "power_in"))
      (node (ref "U221") (pin "5") (pinfunction "GND_5") (pintype "power_in"))
      (node (ref "U221") (pin "7") (pinfunction "GND_7") (pintype "power_in"))
      (node (ref "U301") (pin "10") (pinfunction "GND_10") (pintype "power_in"))
      (node (ref "U301") (pin "6") (pinfunction "IN6_6") (pintype "input"))
      (node (ref "U301") (pin "7") (pinfunction "IN7_7") (pintype "input"))
      (node (ref "U301") (pin "8") (pinfunction "IN8_8") (pintype "input"))
      (node (ref "U501") (pin "10") (pinfunction "T2IN_10") (pintype "input"))
      (node (ref "U501") (pin "15") (pinfunction "GND_15") (pintype "power_in"))
      (node (ref "U501") (pin "8") (pinfunction "R2IN_8") (pintype "input"))
      (node (ref "X111") (pin "6") (pinfunction "6_6") (pintype "passive"))
      (node (ref "X201") (pin "7") (pinfunction "7_7") (pintype "passive"))
      (node (ref "X321") (pin "6") (pinfunction "6_6") (pintype "passive"))
      (node (ref "X321") (pin "7") (pinfunction "7_7") (pintype "passive"))
      (node (ref "X321") (pin "8") (pinfunction "8_8") (pintype "passive"))
      (node (ref "X401") (pin "1") (pinfunction "1_1") (pintype "passive"))
      (node (ref "X401") (pin "6") (pinfunction "6_6") (pintype "passive"))
    )
    (net (code "11") (name "KL") (class "Default")
      (node (ref "K311") (pin "4") (pinfunction "P_4") (pintype "passive"))
      (node (ref "X321") (pin "1") (pinfunction "1_1") (pintype "passive"))
    )
    (net (code "12") (name "M1") (class "Default")
      (node (ref "K314") (pin "4") (pinfunction "P_4") (pintype "passive"))
      (node (ref "X321") (pin "4") (pinfunction "4_4") (pintype "passive"))
    )
    (net (code "13") (name "M2") (class "Default")
      (node (ref "K315") (pin "4") (pinfunction "P_4") (pintype "passive"))
      (node (ref "X321") (pin "5") (pinfunction "5_5") (pintype "passive"))
    )
    (net (code "14") (name "MP_ADC0") (class "Default")
      (node (ref "C631") (pin "1") (pinfunction "1_1") (pintype "passive"))
      (node (ref "R631") (pin "2") (pinfunction "2_2") (pintype "passive"))
      (node (ref "R632") (pin "1") (pinfunction "1_1") (pintype "passive"))
      (node (ref "U101") (pin "23") (pinfunction "PC0(ADC0)_23") (pintype "bidirectional"))
    )
    (net (code "15") (name "MP_ADC1") (class "Default")
      (node (ref "U101") (pin "24") (pinfunction "PC1(ADC1)_24") (pintype "bidirectional"))
    )
    (net (code "16") (name "MP_AVCC") (class "Default")
      (node (ref "L101") (pin "1") (pinfunction "1_1") (pintype "passive"))
      (node (ref "U101") (pin "20") (pinfunction "AVCC_20") (pintype "bidirectional"))
    )
    (net (code "17") (name "MP_FB") (class "Default")
      (node (ref "R122") (pin "1") (pinfunction "1_1") (pintype "passive"))
      (node (ref "R212") (pin "2") (pinfunction "2_2") (pintype "passive"))
      (node (ref "U101") (pin "6") (pinfunction "PD4(XCK/T0)_6") (pintype "bidirectional"))
    )
    (net (code "18") (name "MP_INT") (class "Default")
      (node (ref "U101") (pin "4") (pinfunction "PD2(INT0)_4") (pintype "bidirectional"))
    )
    (net (code "19") (name "MP_KL") (class "Default")
      (node (ref "R135") (pin "2") (pinfunction "2_2") (pintype "passive"))
      (node (ref "U101") (pin "26") (pinfunction "PC3(ADC3)_26") (pintype "bidirectional"))
      (node (ref "U301") (pin "1") (pinfunction "IN1_1") (pintype "input"))
    )
    (net (code "20") (name "MP_M1") (class "Default")
      (node (ref "R133") (pin "2") (pinfunction "2_2") (pintype "passive"))
      (node (ref "U101") (pin "17") (pinfunction "PB3(MOSI/OC2)_17") (pintype "bidirectional"))
      (node (ref "U301") (pin "4") (pinfunction "IN4_4") (pintype "input"))
    )
    (net (code "21") (name "MP_M2") (class "Default")
      (node (ref "R134") (pin "2") (pinfunction "2_2") (pintype "passive"))
      (node (ref "U101") (pin "16") (pinfunction "PB2(SS/OC1B)_16") (pintype "bidirectional"))
      (node (ref "U301") (pin "5") (pinfunction "IN5_5") (pintype "input"))
    )
    (net (code "22") (name "MP_PV_G") (class "Default")
      (node (ref "R131") (pin "2") (pinfunction "2_2") (pintype "passive"))
      (node (ref "U101") (pin "19") (pinfunction "PB5(SCK)_19") (pintype "bidirectional"))
      (node (ref "U301") (pin "2") (pinfunction "IN2_2") (pintype "input"))
    )
    (net (code "23") (name "MP_PV_O") (class "Default")
      (node (ref "R132") (pin "2") (pinfunction "2_2") (pintype "passive"))
      (node (ref "U101") (pin "18") (pinfunction "PB4(MISO)_18") (pintype "bidirectional"))
      (node (ref "U301") (pin "3") (pinfunction "IN3_3") (pintype "input"))
    )
    (net (code "24") (name "MP_RXD") (class "Default")
      (node (ref "U101") (pin "2") (pinfunction "PD0(RXD)_2") (pintype "bidirectional"))
      (node (ref "U501") (pin "12") (pinfunction "R1OUT_12") (pintype "output"))
    )
    (net (code "25") (name "MP_SA_G") (class "Default")
      (node (ref "R125") (pin "1") (pinfunction "1_1") (pintype "passive"))
      (node (ref "R215") (pin "2") (pinfunction "2_2") (pintype "passive"))
      (node (ref "U101") (pin "12") (pinfunction "PD6(AIN0)_12") (pintype "bidirectional"))
      (node (ref "U221") (pin "2") (pinfunction "C_2") (pintype "passive"))
    )
    (net (code "26") (name "MP_SA_O") (class "Default")
      (node (ref "R126") (pin "1") (pinfunction "1_1") (pintype "passive"))
      (node (ref "R216") (pin "2") (pinfunction "2_2") (pintype "passive"))
      (node (ref "U101") (pin "13") (pinfunction "PD7(AIN1)_13") (pintype "bidirectional"))
      (node (ref "U221") (pin "4") (pinfunction "D_4") (pintype "passive"))
    )
    (net (code "27") (name "MP_SK_G") (class "Default")
      (node (ref "R123") (pin "2") (pinfunction "2_2") (pintype "passive"))
      (node (ref "R213") (pin "2") (pinfunction "2_2") (pintype "passive"))
      (node (ref "U101") (pin "9") (pinfunction "PB6(XTAL1/TOSC1)_9") (pintype "bidirectional"))
      (node (ref "U221") (pin "8") (pinfunction "A_8") (pintype "passive"))
    )
    (net (code "28") (name "MP_SK_O") (class "Default")
      (node (ref "R124") (pin "2") (pinfunction "2_2") (pintype "passive"))
      (node (ref "R214") (pin "2") (pinfunction "2_2") (pintype "passive"))
      (node (ref "U101") (pin "10") (pinfunction "PB7(XTAL2/TOSC2)_10") (pintype "bidirectional"))
      (node (ref "U221") (pin "6") (pinfunction "B_6") (pintype "passive"))
    )
    (net (code "29") (name "MP_TACHO") (class "Default")
      (node (ref "R211") (pin "1") (pinfunction "1_1") (pintype "passive"))
      (node (ref "R231") (pin "2") (pinfunction "2_2") (pintype "passive"))
      (node (ref "U101") (pin "25") (pinfunction "PC2(ADC2)_25") (pintype "bidirectional"))
    )
    (net (code "30") (name "MP_TXD") (class "Default")
      (node (ref "U101") (pin "3") (pinfunction "PD1(TXD)_3") (pintype "bidirectional"))
      (node (ref "U501") (pin "11") (pinfunction "T1IN_11") (pintype "input"))
    )
    (net (code "31") (name "MX_C1P") (class "Default")
      (node (ref "C501") (pin "1") (pinfunction "1_1") (pintype "passive"))
      (node (ref "U501") (pin "1") (pinfunction "C1+_1") (pintype "bidirectional"))
    )
    (net (code "32") (name "MX_C2P") (class "Default")
      (node (ref "C502") (pin "1") (pinfunction "1_1") (pintype "passive"))
      (node (ref "U501") (pin "4") (pinfunction "C2+_4") (pintype "bidirectional"))
    )
    (net (code "33") (name "MX_VM") (class "Default")
      (node (ref "C504") (pin "1") (pinfunction "1_1") (pintype "passive"))
      (node (ref "U501") (pin "6") (pinfunction "V-_6") (pintype "bidirectional"))
    )
    (net (code "34") (name "MX_VP") (class "Default")
      (node (ref "C503") (pin "1") (pinfunction "1_1") (pintype "passive"))
      (node (ref "U501") (pin "2") (pinfunction "V+_2") (pintype "bidirectional"))
    )
    (net (code "35") (name "Net-(D141-PadA)") (class "Default")
      (node (ref "D141") (pin "A") (pinfunction "A_A") (pintype "passive"))
      (node (ref "R141") (pin "2") (pinfunction "2_2") (pintype "passive"))
    )
    (net (code "36") (name "Net-(U101-AREF)") (class "Default")
      (node (ref "C102") (pin "2") (pinfunction "2_2") (pintype "passive"))
      (node (ref "U101") (pin "21") (pinfunction "AREF_21") (pintype "bidirectional"))
    )
    (net (code "37") (name "Net-(U101-PD3(INT1))") (class "Default")
      (node (ref "R141") (pin "1") (pinfunction "1_1") (pintype "passive"))
      (node (ref "U101") (pin "5") (pinfunction "PD3(INT1)_5") (pintype "bidirectional"))
    )
    (net (code "38") (name "Net-(U501A-C1-)") (class "Default")
      (node (ref "C501") (pin "2") (pinfunction "2_2") (pintype "passive"))
      (node (ref "U501") (pin "3") (pinfunction "C1-_3") (pintype "bidirectional"))
    )
    (net (code "39") (name "Net-(U501A-C2-)") (class "Default")
      (node (ref "C502") (pin "2") (pinfunction "2_2") (pintype "passive"))
      (node (ref "U501") (pin "5") (pinfunction "C2-_5") (pintype "bidirectional"))
    )
    (net (code "40") (name "PV_G") (class "Default")
      (node (ref "K312") (pin "4") (pinfunction "P_4") (pintype "passive"))
      (node (ref "X321") (pin "2") (pinfunction "2_2") (pintype "passive"))
    )
    (net (code "41") (name "PV_O") (class "Default")
      (node (ref "K313") (pin "4") (pinfunction "P_4") (pintype "passive"))
      (node (ref "X321") (pin "3") (pinfunction "3_3") (pintype "passive"))
    )
    (net (code "42") (name "REGIN") (class "Default")
      (node (ref "C601") (pin "+") (pinfunction "+_+") (pintype "passive"))
      (node (ref "C602") (pin "1") (pinfunction "1_1") (pintype "passive"))
      (node (ref "D601") (pin "C") (pinfunction "C_C") (pintype "passive"))
      (node (ref "F602") (pin "3") (pinfunction "2_3") (pintype "passive"))
      (node (ref "F602") (pin "4") (pinfunction "2_4") (pintype "passive"))
      (node (ref "IC611") (pin "1") (pinfunction "VI_1") (pintype "input"))
    )
    (net (code "43") (name "RXD") (class "Default")
      (node (ref "U501") (pin "13") (pinfunction "R1IN_13") (pintype "input"))
      (node (ref "X511") (pin "2") (pinfunction "2_2") (pintype "passive"))
    )
    (net (code "44") (name "SA_G") (class "Default")
      (node (ref "R215") (pin "1") (pinfunction "1_1") (pintype "passive"))
      (node (ref "X201") (pin "5") (pinfunction "5_5") (pintype "passive"))
    )
    (net (code "45") (name "SA_O") (class "Default")
      (node (ref "R216") (pin "1") (pinfunction "1_1") (pintype "passive"))
      (node (ref "X201") (pin "6") (pinfunction "6_6") (pintype "passive"))
    )
    (net (code "46") (name "SCL") (class "Default")
      (node (ref "R491") (pin "1") (pinfunction "1_1") (pintype "passive"))
      (node (ref "U101") (pin "28") (pinfunction "PC5(ADC5/SCL)_28") (pintype "bidirectional"))
      (node (ref "X401") (pin "2") (pinfunction "2_2") (pintype "passive"))
    )
    (net (code "47") (name "SDA") (class "Default")
      (node (ref "R492") (pin "1") (pinfunction "1_1") (pintype "passive"))
      (node (ref "U101") (pin "27") (pinfunction "PC4(ADC4/SDA)_27") (pintype "bidirectional"))
      (node (ref "X401") (pin "4") (pinfunction "4_4") (pintype "passive"))
    )
    (net (code "48") (name "SK_G") (class "Default")
      (node (ref "R213") (pin "1") (pinfunction "1_1") (pintype "passive"))
      (node (ref "X201") (pin "3") (pinfunction "3_3") (pintype "passive"))
    )
    (net (code "49") (name "SK_O") (class "Default")
      (node (ref "R214") (pin "1") (pinfunction "1_1") (pintype "passive"))
      (node (ref "X201") (pin "4") (pinfunction "4_4") (pintype "passive"))
    )
    (net (code "50") (name "TACHO") (class "Default")
      (node (ref "R211") (pin "2") (pinfunction "2_2") (pintype "passive"))
      (node (ref "X201") (pin "1") (pinfunction "1_1") (pintype "passive"))
    )
    (net (code "51") (name "TXD") (class "Default")
      (node (ref "U501") (pin "14") (pinfunction "T1OUT_14") (pintype "output"))
      (node (ref "X511") (pin "1") (pinfunction "1_1") (pintype "passive"))
    )
    (net (code "52") (name "unconnected-(K311B-O-Pad3)") (class "Default")
      (node (ref "K311") (pin "3") (pinfunction "O_3") (pintype "passive"))
    )
    (net (code "53") (name "unconnected-(K312B-O-Pad3)") (class "Default")
      (node (ref "K312") (pin "3") (pinfunction "O_3") (pintype "passive"))
    )
    (net (code "54") (name "unconnected-(K313B-O-Pad3)") (class "Default")
      (node (ref "K313") (pin "3") (pinfunction "O_3") (pintype "passive"))
    )
    (net (code "55") (name "unconnected-(U101-PB0(ICP)-Pad14)") (class "Default")
      (node (ref "U101") (pin "14") (pinfunction "PB0(ICP)_14") (pintype "bidirectional"))
    )
    (net (code "56") (name "unconnected-(U101-PB1(OC1A)-Pad15)") (class "Default")
      (node (ref "U101") (pin "15") (pinfunction "PB1(OC1A)_15") (pintype "bidirectional"))
    )
    (net (code "57") (name "unconnected-(U101-PD5(T1)-Pad11)") (class "Default")
      (node (ref "U101") (pin "11") (pinfunction "PD5(T1)_11") (pintype "bidirectional"))
    )
    (net (code "58") (name "unconnected-(U301-OUT6-Pad13)") (class "Default")
      (node (ref "U301") (pin "13") (pinfunction "OUT6_13") (pintype "open_collector"))
    )
    (net (code "59") (name "unconnected-(U301-OUT7-Pad12)") (class "Default")
      (node (ref "U301") (pin "12") (pinfunction "OUT7_12") (pintype "open_collector"))
    )
    (net (code "60") (name "unconnected-(U301-OUT8-Pad11)") (class "Default")
      (node (ref "U301") (pin "11") (pinfunction "OUT8_11") (pintype "open_collector"))
    )
    (net (code "61") (name "unconnected-(U501A-R2OUT-Pad9)") (class "Default")
      (node (ref "U501") (pin "9") (pinfunction "R2OUT_9") (pintype "output"))
    )
    (net (code "62") (name "unconnected-(U501A-T2OUT-Pad7)") (class "Default")
      (node (ref "U501") (pin "7") (pinfunction "T2OUT_7") (pintype "output"))
    )
    (net (code "63") (name "unconnected-(X111-Pad1)") (class "Default")
      (node (ref "X111") (pin "1") (pinfunction "1_1") (pintype "passive"))
    )
    (net (code "64") (name "unconnected-(X111-Pad3)") (class "Default")
      (node (ref "X111") (pin "3") (pinfunction "3_3") (pintype "passive"))
    )
    (net (code "65") (name "unconnected-(X111-Pad4)") (class "Default")
      (node (ref "X111") (pin "4") (pinfunction "4_4") (pintype "passive"))
    )
    (net (code "66") (name "unconnected-(X401-Pad5)") (class "Default")
      (node (ref "X401") (pin "5") (pinfunction "5_5") (pintype "passive"))
    )
    (net (code "67") (name "unconnected-(X511-Pad3)") (class "Default")
      (node (ref "X511") (pin "3") (pinfunction "3_3") (pintype "passive"))
    )
    (net (code "68") (name "unconnected-(X511-Pad4)") (class "Default")
      (node (ref "X511") (pin "4") (pinfunction "4_4") (pintype "passive"))
    )
    (net (code "69") (name "~{RST}") (class "Default")
      (node (ref "R101") (pin "2") (pinfunction "2_2") (pintype "passive"))
      (node (ref "U101") (pin "1") (pinfunction "PC6(/RESET)_1") (pintype "bidirectional"))
      (node (ref "X111") (pin "5") (pinfunction "5_5") (pintype "passive"))
    )
  )
)
